# simple-differential-electrostatic-rev1.net
KiCad netlist of a schematic drawn in EAGLE
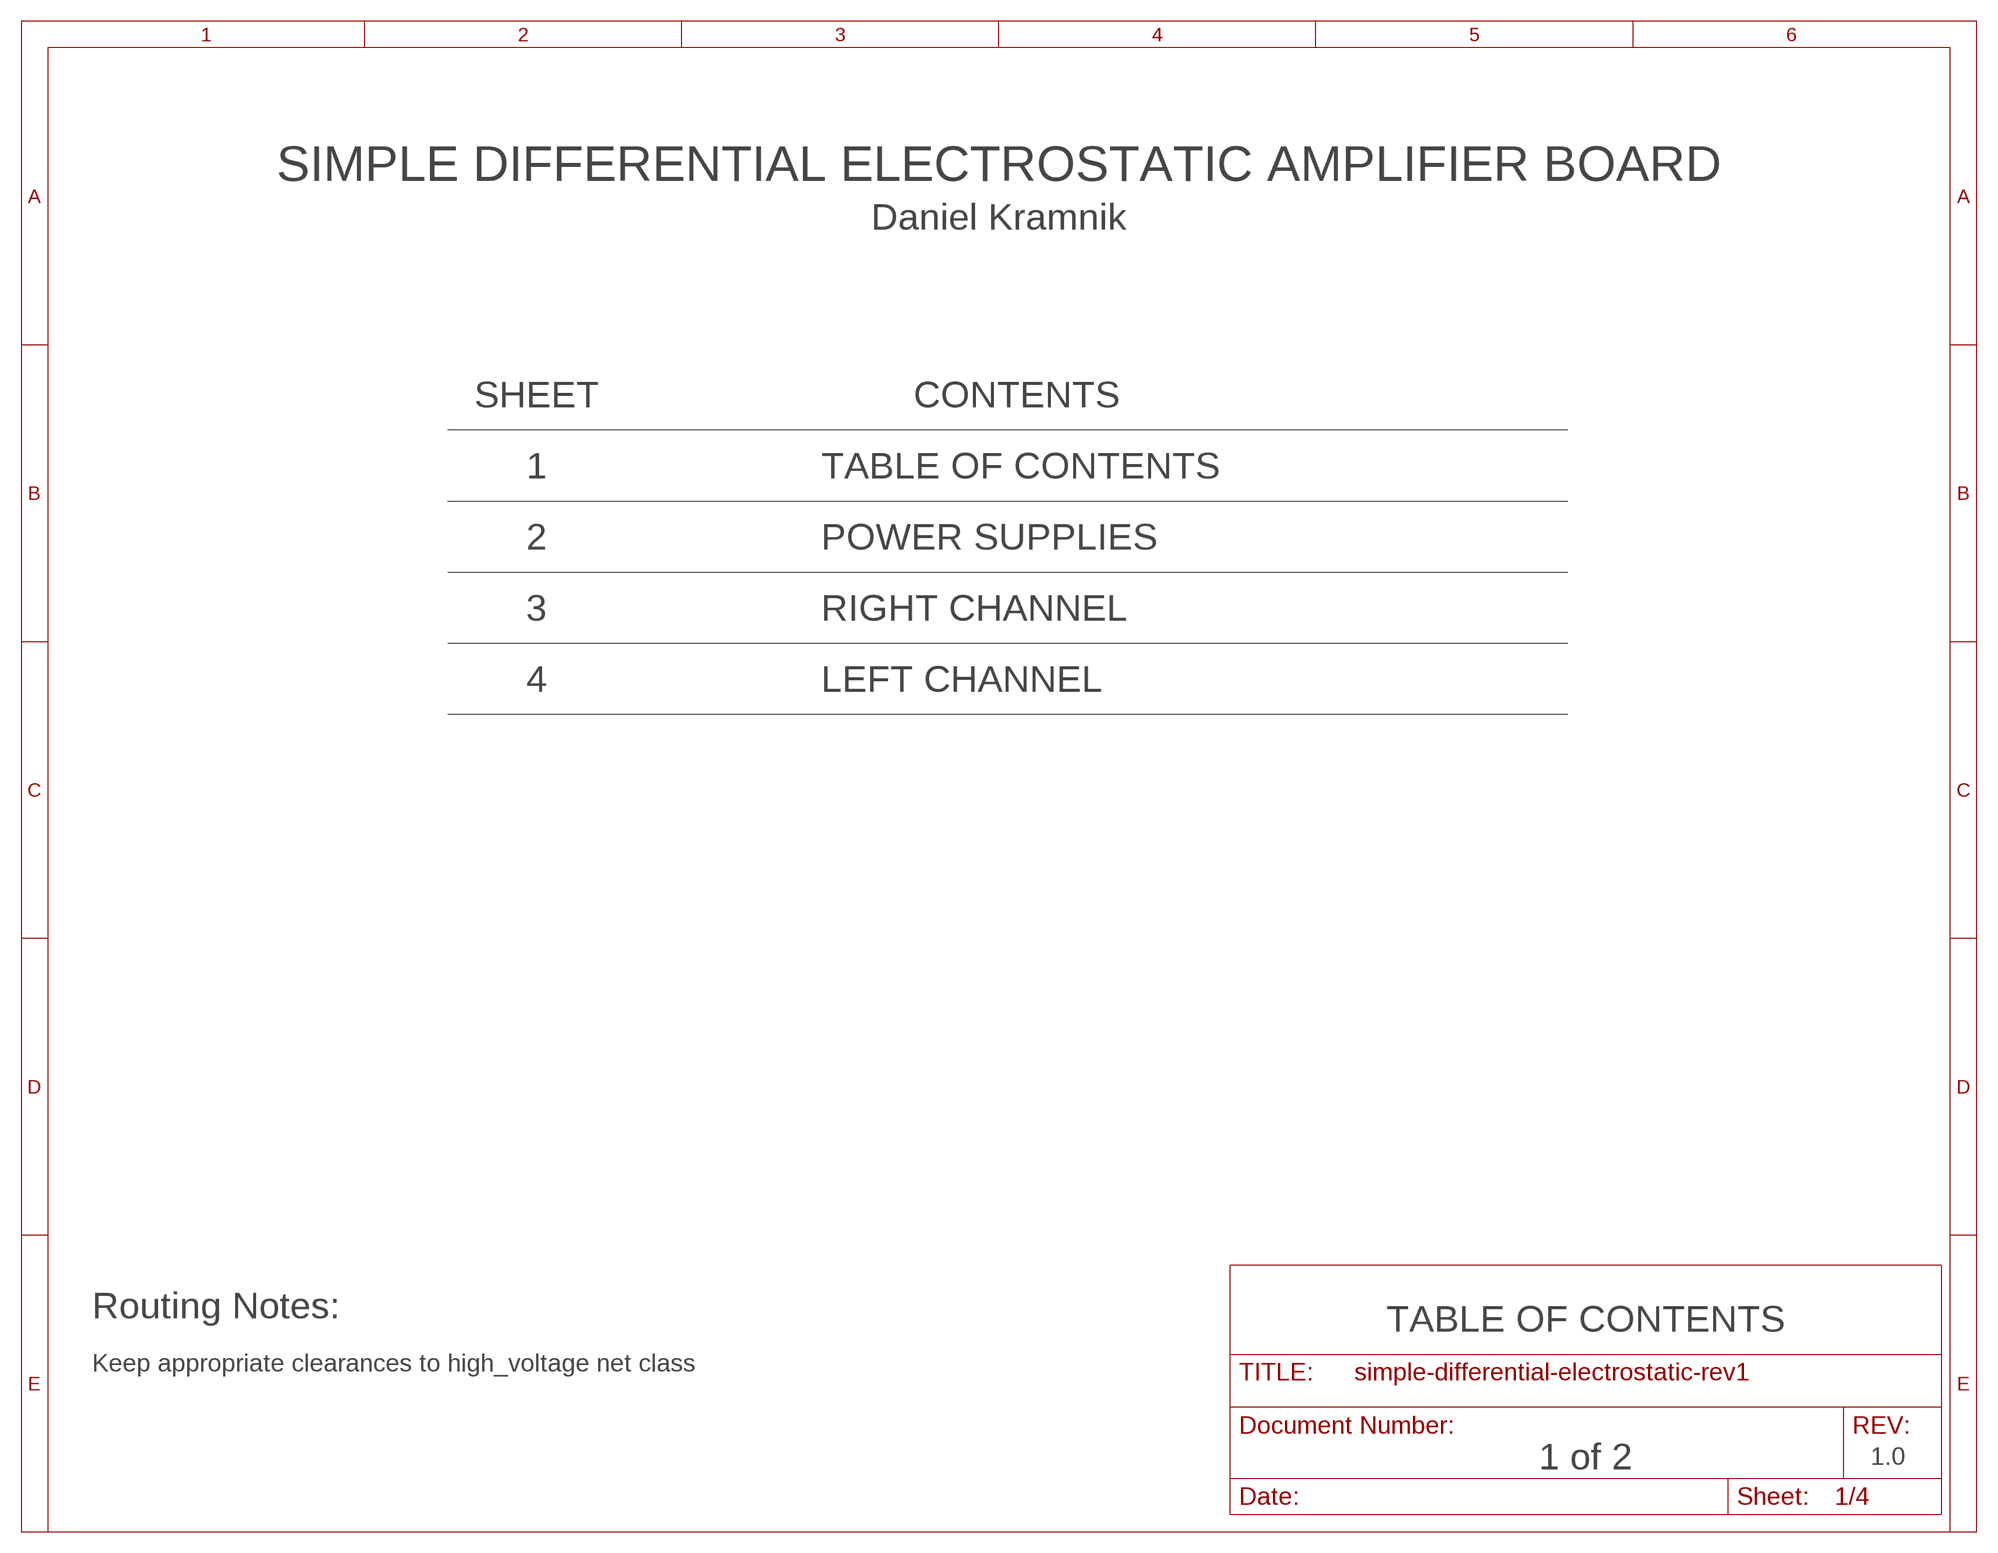
[diagram p0: schematic, sheet 1]
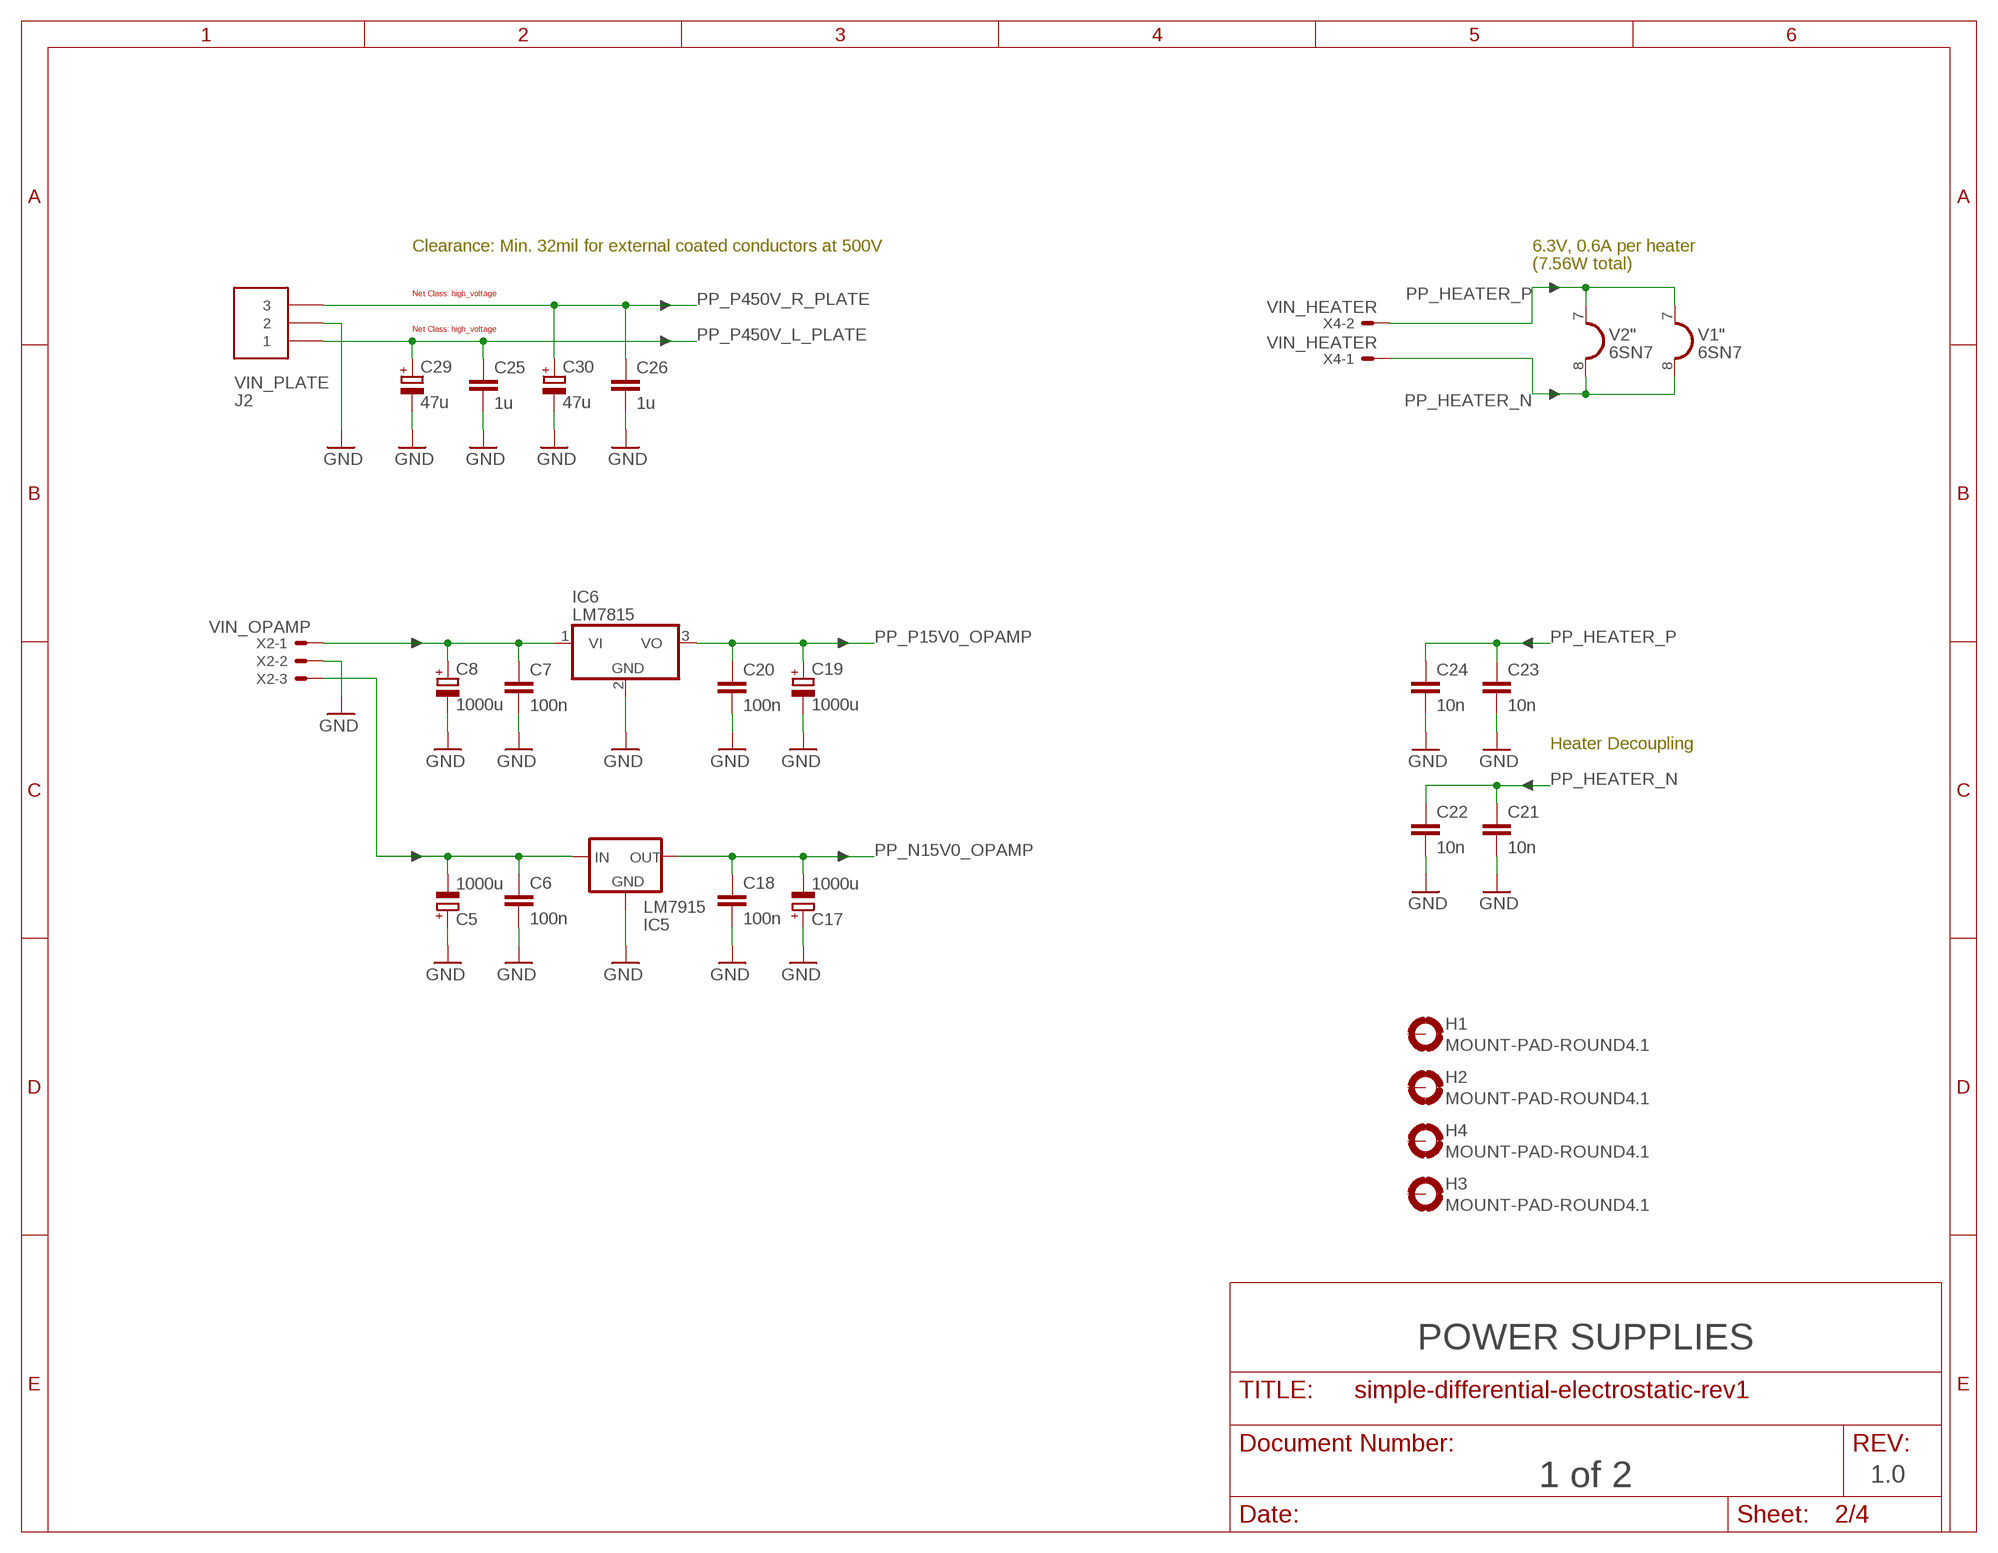
[diagram p1: schematic, sheet 2]
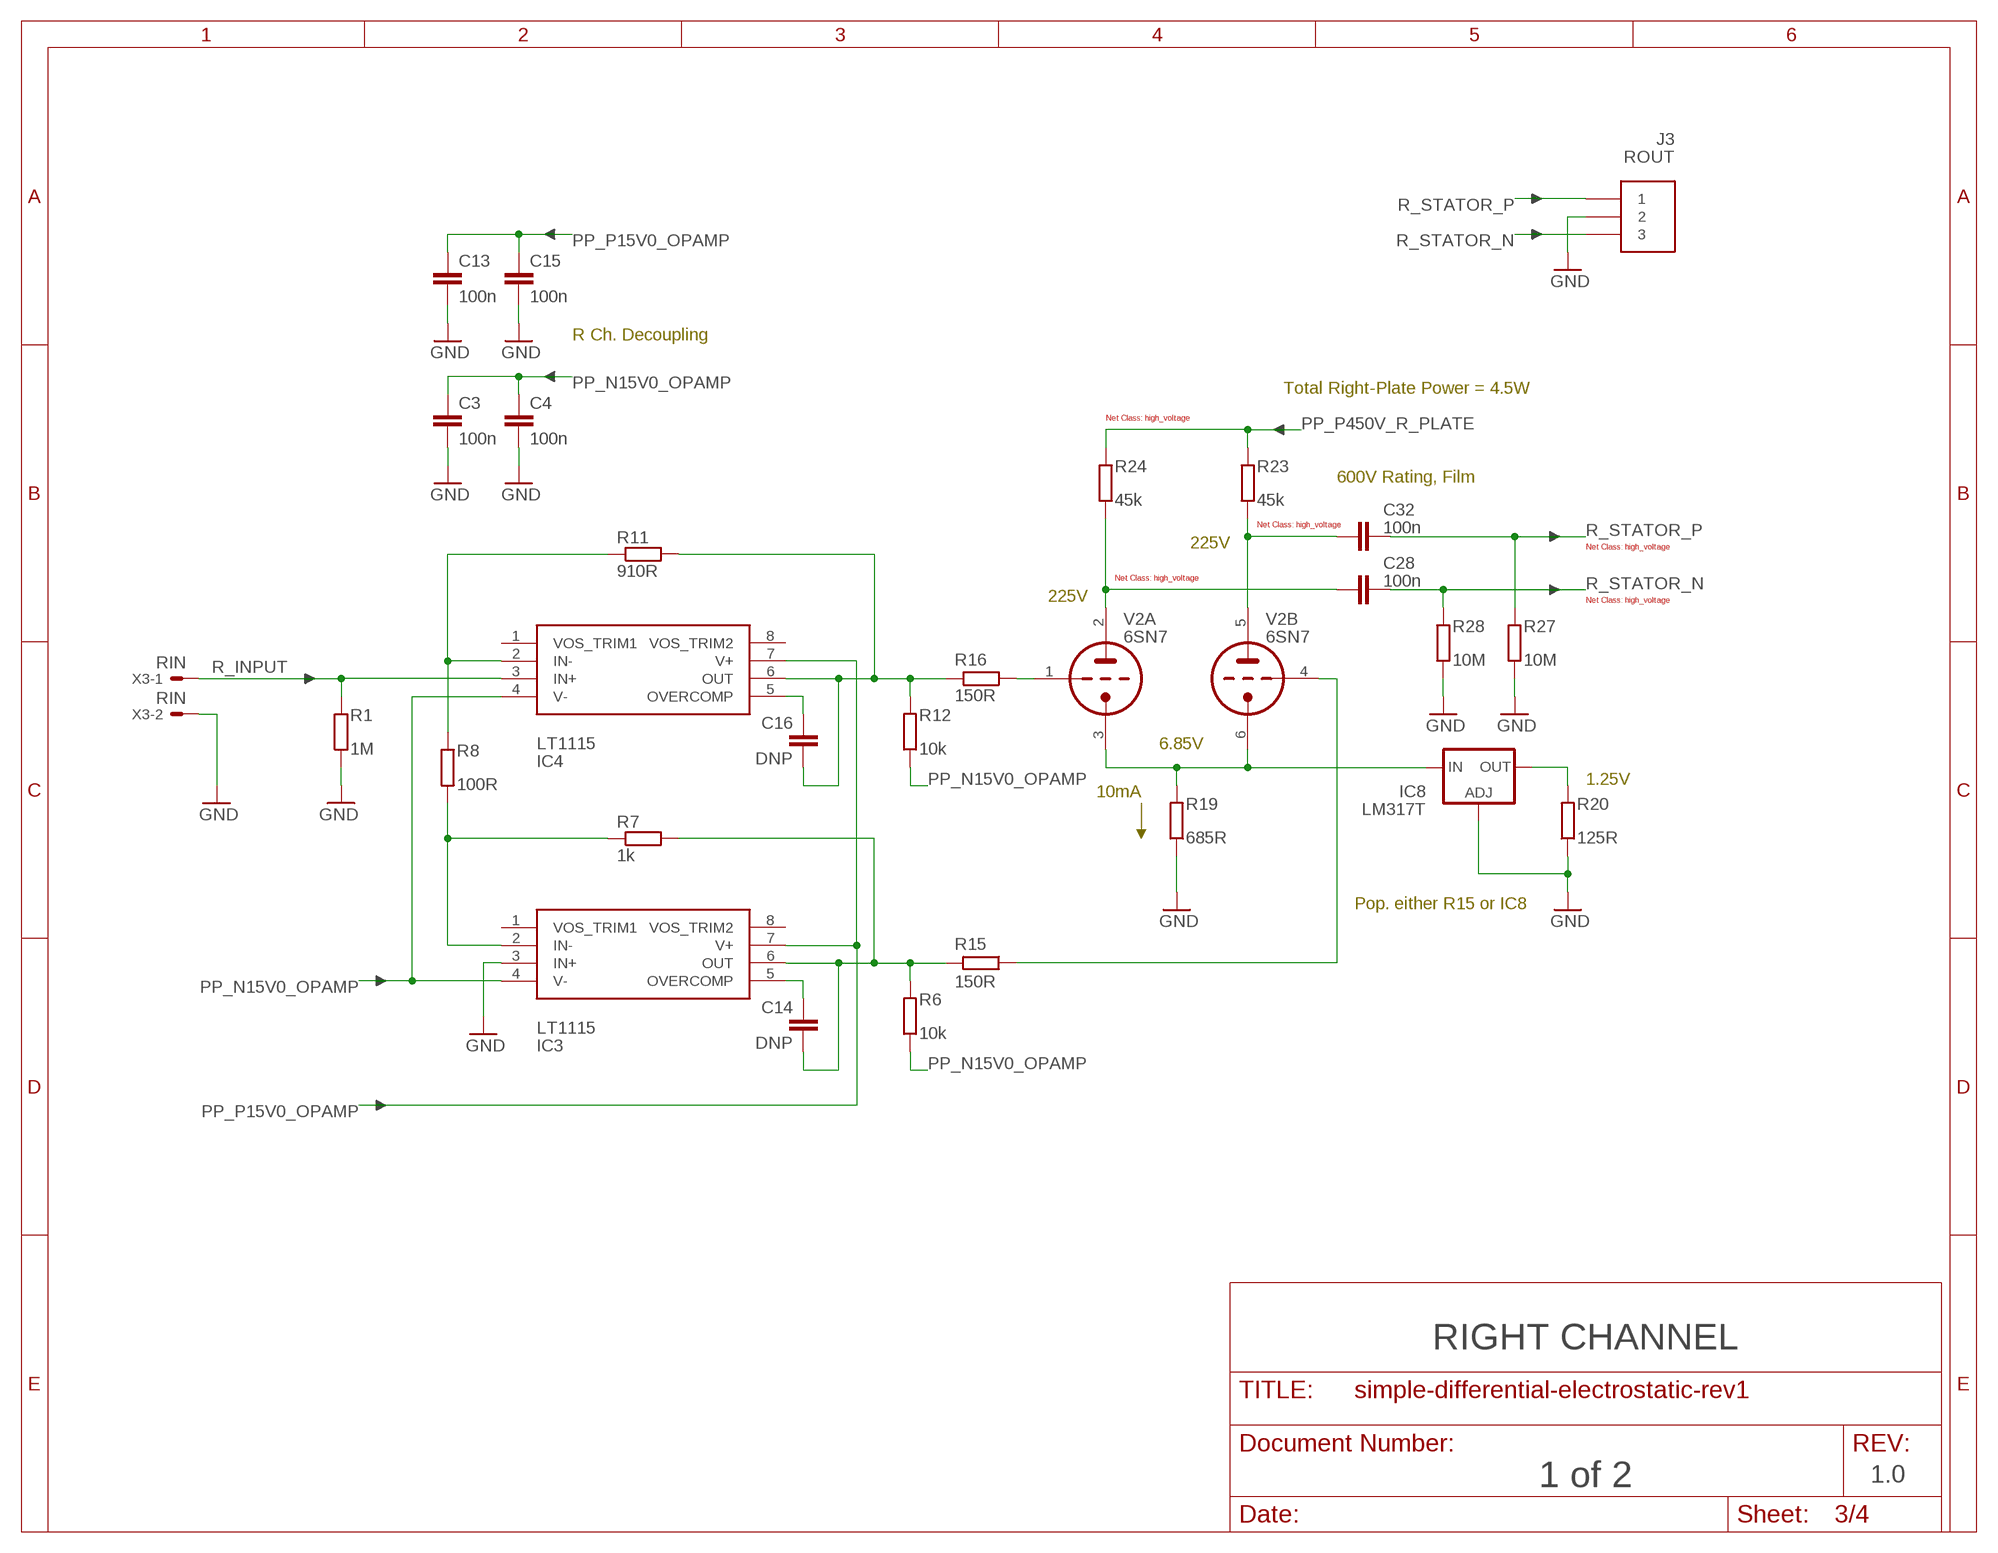
[diagram p2: schematic, sheet 3]
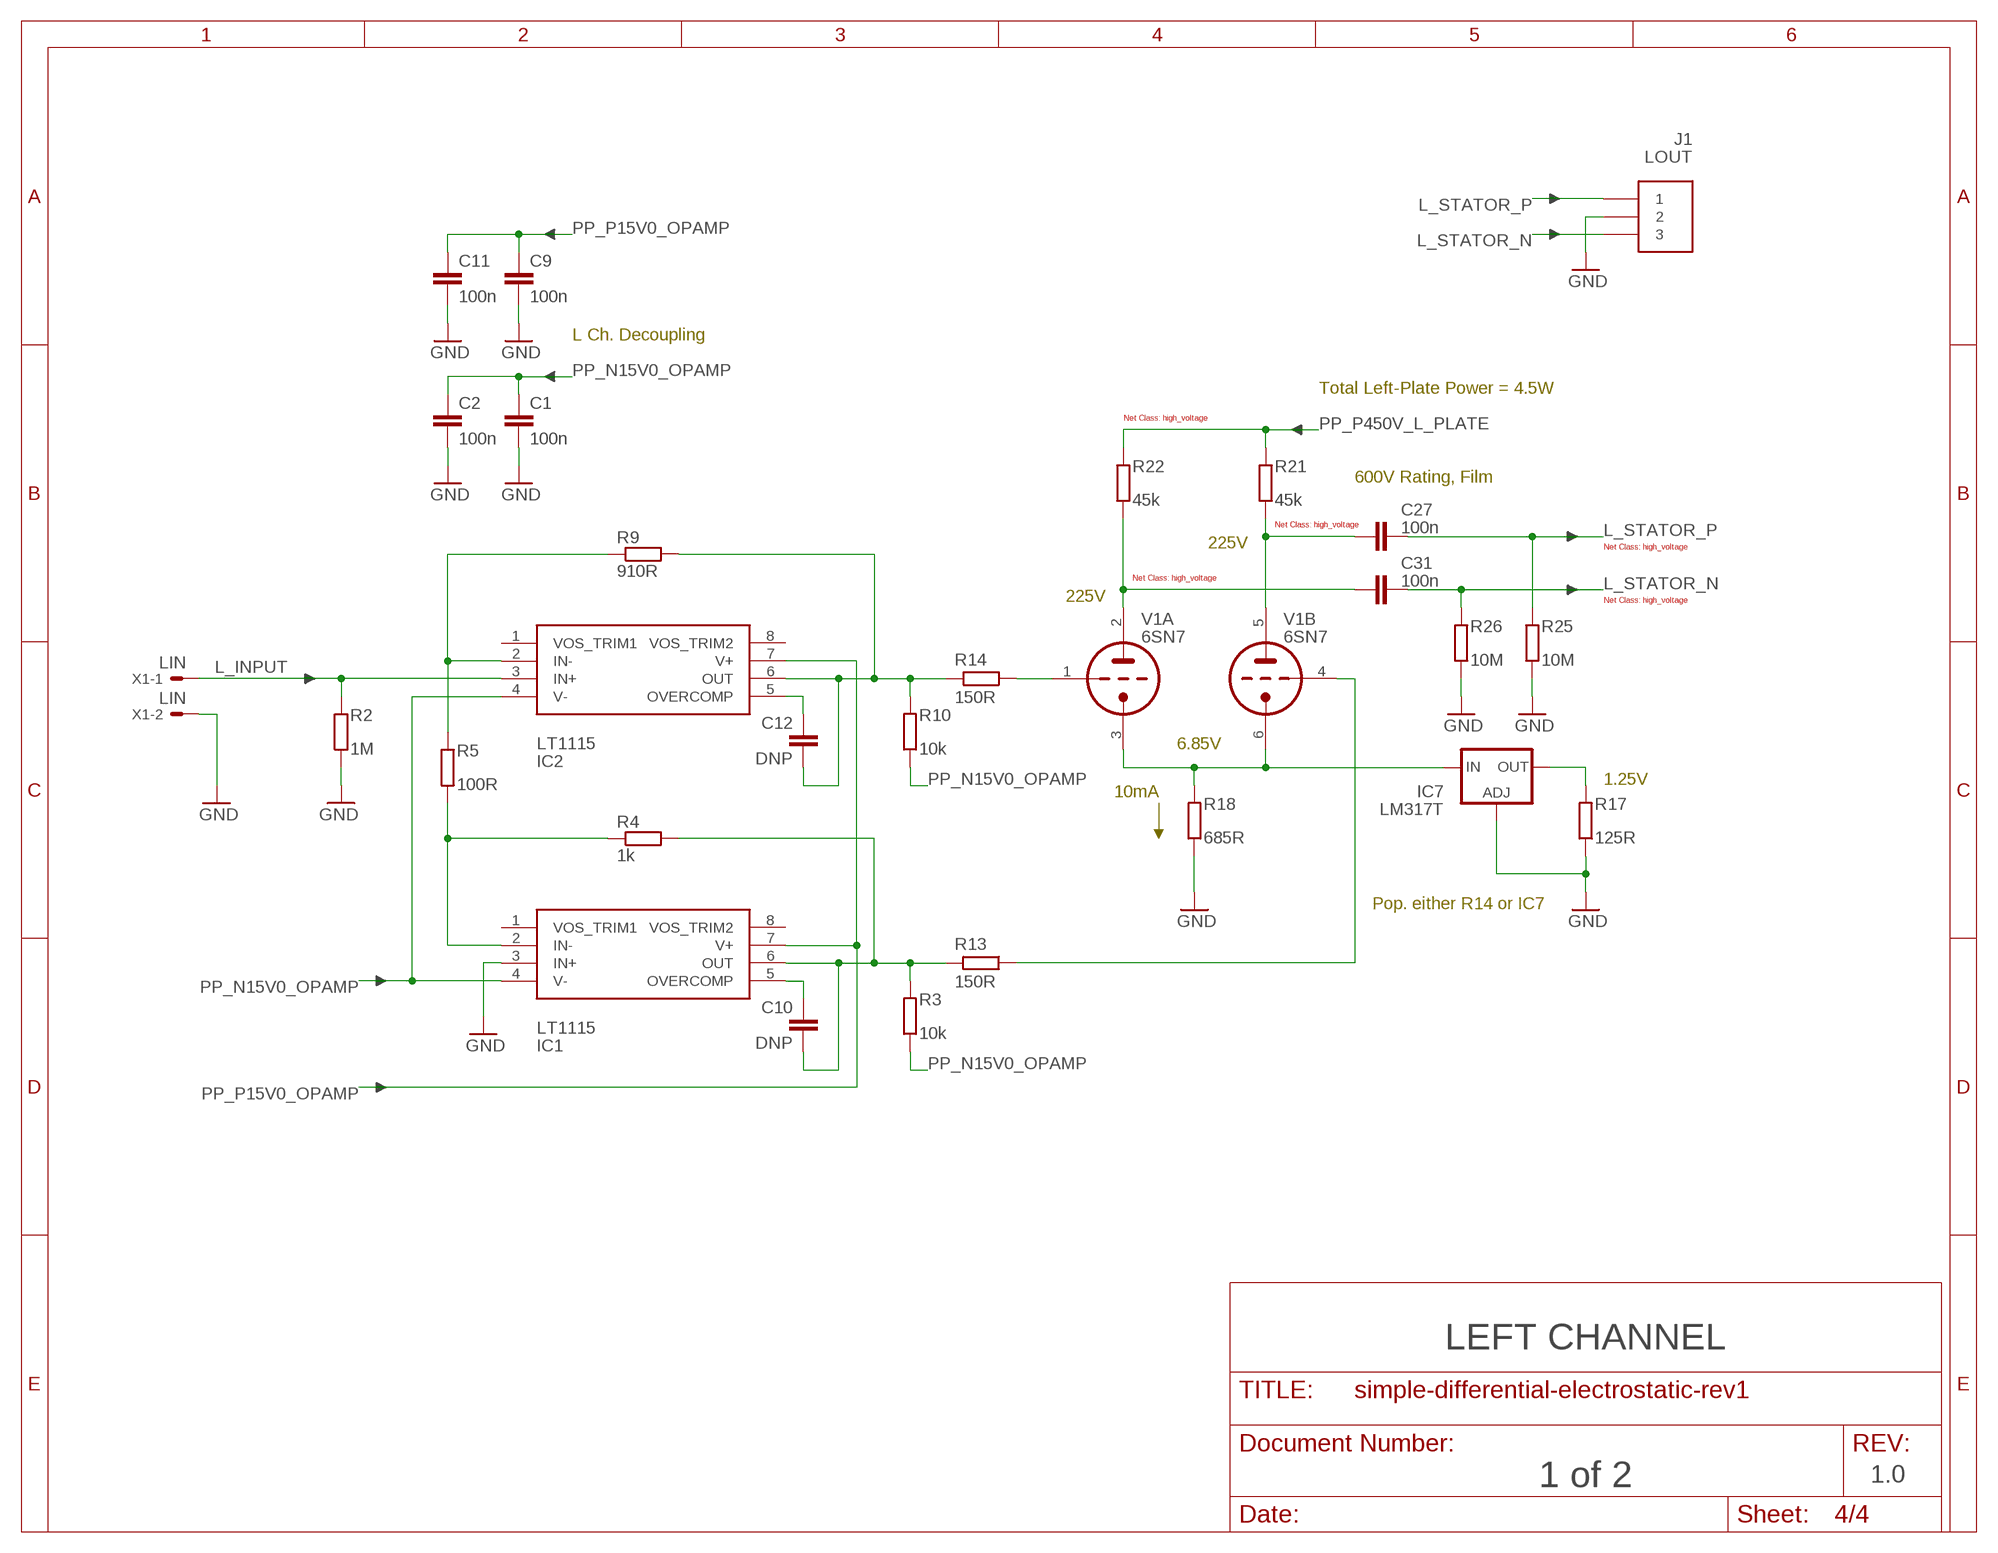
[diagram p3: schematic, sheet 4]

(export (version "E")
  (design (tool "Eeschema 10.0.6"))
  (components
    (comp (ref "C3")
      (value "100n")
      (footprint "eagle-import:C050-025X075")
      (libsource (lib "eagle-import") (part "C-EU050-025X075"))
    )
    (comp (ref "C4")
      (value "100n")
      (footprint "eagle-import:C050-025X075")
      (libsource (lib "eagle-import") (part "C-EU050-025X075"))
    )
    (comp (ref "C13")
      (value "100n")
      (footprint "eagle-import:C050-025X075")
      (libsource (lib "eagle-import") (part "C-EU050-025X075"))
    )
    (comp (ref "C14")
      (value "DNP")
      (footprint "eagle-import:C050-025X075")
      (libsource (lib "eagle-import") (part "C-EU050-025X075"))
    )
    (comp (ref "C15")
      (value "100n")
      (footprint "eagle-import:C050-025X075")
      (libsource (lib "eagle-import") (part "C-EU050-025X075"))
    )
    (comp (ref "C16")
      (value "DNP")
      (footprint "eagle-import:C050-025X075")
      (libsource (lib "eagle-import") (part "C-EU050-025X075"))
    )
    (comp (ref "C28")
      (value "100n")
      (footprint "eagle-import:C375-155X418")
      (libsource (lib "eagle-import") (part "C-EU375-155X418"))
    )
    (comp (ref "C32")
      (value "100n")
      (footprint "eagle-import:C375-155X418")
      (libsource (lib "eagle-import") (part "C-EU375-155X418"))
    )
    (comp (ref "IC3")
      (value "LT1115")
      (footprint "eagle-import:DIL08")
      (libsource (lib "eagle-import") (part "LT1115"))
    )
    (comp (ref "IC4")
      (value "LT1115")
      (footprint "eagle-import:DIL08")
      (libsource (lib "eagle-import") (part "LT1115"))
    )
    (comp (ref "IC8")
      (value "LM317T")
      (footprint "eagle-import:317TS")
      (libsource (lib "eagle-import") (part "LM317TS"))
    )
    (comp (ref "J3")
      (value "ROUT")
      (footprint "eagle-import:CONN_MOLEX_3PIN_MINI-FIT_JR")
      (libsource (lib "eagle-import") (part "CONN_MOLEX_3PIN_MINI-FIT_JR"))
    )
    (comp (ref "R1")
      (value "1M")
      (footprint "eagle-import:0309_10")
      (libsource (lib "eagle-import") (part "R-EU_0309/10"))
    )
    (comp (ref "R6")
      (value "10k")
      (footprint "eagle-import:0309_10")
      (libsource (lib "eagle-import") (part "R-EU_0309/10"))
    )
    (comp (ref "R7")
      (value "1k")
      (footprint "eagle-import:0309_10")
      (libsource (lib "eagle-import") (part "R-EU_0309/10"))
    )
    (comp (ref "R8")
      (value "100R")
      (footprint "eagle-import:0309_10")
      (libsource (lib "eagle-import") (part "R-EU_0309/10"))
    )
    (comp (ref "R11")
      (value "910R")
      (footprint "eagle-import:0309_10")
      (libsource (lib "eagle-import") (part "R-EU_0309/10"))
    )
    (comp (ref "R12")
      (value "10k")
      (footprint "eagle-import:0309_10")
      (libsource (lib "eagle-import") (part "R-EU_0309/10"))
    )
    (comp (ref "R15")
      (value "150R")
      (footprint "eagle-import:0309_10")
      (libsource (lib "eagle-import") (part "R-EU_0309/10"))
    )
    (comp (ref "R16")
      (value "150R")
      (footprint "eagle-import:0309_10")
      (libsource (lib "eagle-import") (part "R-EU_0309/10"))
    )
    (comp (ref "R19")
      (value "685R")
      (footprint "eagle-import:0309_10")
      (libsource (lib "eagle-import") (part "R-EU_0309/10"))
    )
    (comp (ref "R20")
      (value "125R")
      (footprint "eagle-import:0309_10")
      (libsource (lib "eagle-import") (part "R-EU_0309/10"))
    )
    (comp (ref "R23")
      (value "45k")
      (footprint "eagle-import:P0613_15")
      (libsource (lib "eagle-import") (part "R-EU_0613/15"))
    )
    (comp (ref "R24")
      (value "45k")
      (footprint "eagle-import:P0613_15")
      (libsource (lib "eagle-import") (part "R-EU_0613/15"))
    )
    (comp (ref "R27")
      (value "10M")
      (footprint "eagle-import:0309_10")
      (libsource (lib "eagle-import") (part "R-EU_0309/10"))
    )
    (comp (ref "R28")
      (value "10M")
      (footprint "eagle-import:0309_10")
      (libsource (lib "eagle-import") (part "R-EU_0309/10"))
    )
    (comp (ref "V2")
      (value "6SN7")
      (footprint "eagle-import:OKTAL")
      (libsource (lib "eagle-import") (part "6SN7GT-P"))
    )
    (comp (ref "X3")
      (value "RIN")
      (footprint "eagle-import:KK-156-2")
      (libsource (lib "eagle-import") (part "KK-156-2"))
    )
    (comp (ref "C5")
      (value "1000u")
      (footprint "eagle-import:E5-10,5")
      (libsource (lib "eagle-import") (part "CPOL-EUE5-10.5"))
    )
    (comp (ref "C6")
      (value "100n")
      (footprint "eagle-import:C050-025X075")
      (libsource (lib "eagle-import") (part "C-EU050-025X075"))
    )
    (comp (ref "C7")
      (value "100n")
      (footprint "eagle-import:C050-025X075")
      (libsource (lib "eagle-import") (part "C-EU050-025X075"))
    )
    (comp (ref "C8")
      (value "1000u")
      (footprint "eagle-import:E5-10,5")
      (libsource (lib "eagle-import") (part "CPOL-EUE5-10.5"))
    )
    (comp (ref "C17")
      (value "1000u")
      (footprint "eagle-import:E5-10,5")
      (libsource (lib "eagle-import") (part "CPOL-EUE5-10.5"))
    )
    (comp (ref "C18")
      (value "100n")
      (footprint "eagle-import:C050-025X075")
      (libsource (lib "eagle-import") (part "C-EU050-025X075"))
    )
    (comp (ref "C19")
      (value "1000u")
      (footprint "eagle-import:E5-10,5")
      (libsource (lib "eagle-import") (part "CPOL-EUE5-10.5"))
    )
    (comp (ref "C20")
      (value "100n")
      (footprint "eagle-import:C050-025X075")
      (libsource (lib "eagle-import") (part "C-EU050-025X075"))
    )
    (comp (ref "C21")
      (value "10n")
      (footprint "eagle-import:C050-025X075")
      (libsource (lib "eagle-import") (part "C-EU050-025X075"))
    )
    (comp (ref "C22")
      (value "10n")
      (footprint "eagle-import:C050-025X075")
      (libsource (lib "eagle-import") (part "C-EU050-025X075"))
    )
    (comp (ref "C23")
      (value "10n")
      (footprint "eagle-import:C050-025X075")
      (libsource (lib "eagle-import") (part "C-EU050-025X075"))
    )
    (comp (ref "C24")
      (value "10n")
      (footprint "eagle-import:C050-025X075")
      (libsource (lib "eagle-import") (part "C-EU050-025X075"))
    )
    (comp (ref "C25")
      (value "1u")
      (footprint "eagle-import:C325-137X374")
      (libsource (lib "eagle-import") (part "C-EU325-137X374"))
    )
    (comp (ref "C26")
      (value "1u")
      (footprint "eagle-import:C325-137X374")
      (libsource (lib "eagle-import") (part "C-EU325-137X374"))
    )
    (comp (ref "C29")
      (value "47u")
      (footprint "eagle-import:EB22,5D")
      (libsource (lib "eagle-import") (part "CPOL-EUE10-22.5"))
    )
    (comp (ref "C30")
      (value "47u")
      (footprint "eagle-import:EB22,5D")
      (libsource (lib "eagle-import") (part "CPOL-EUE10-22.5"))
    )
    (comp (ref "H1")
      (value "MOUNT-PAD-ROUND4.1")
      (footprint "eagle-import:4,1-PAD")
      (libsource (lib "eagle-import") (part "MOUNT-PAD-ROUND4.1"))
    )
    (comp (ref "H2")
      (value "MOUNT-PAD-ROUND4.1")
      (footprint "eagle-import:4,1-PAD")
      (libsource (lib "eagle-import") (part "MOUNT-PAD-ROUND4.1"))
    )
    (comp (ref "H3")
      (value "MOUNT-PAD-ROUND4.1")
      (footprint "eagle-import:4,1-PAD")
      (libsource (lib "eagle-import") (part "MOUNT-PAD-ROUND4.1"))
    )
    (comp (ref "H4")
      (value "MOUNT-PAD-ROUND4.1")
      (footprint "eagle-import:4,1-PAD")
      (libsource (lib "eagle-import") (part "MOUNT-PAD-ROUND4.1"))
    )
    (comp (ref "IC5")
      (value "LM7915")
      (footprint "eagle-import:79XXS")
      (libsource (lib "eagle-import") (part "79XXS"))
    )
    (comp (ref "IC6")
      (value "LM7815")
      (footprint "eagle-import:TO220V")
      (libsource (lib "eagle-import") (part "78TV15"))
    )
    (comp (ref "J2")
      (value "VIN_PLATE")
      (footprint "eagle-import:CONN_MOLEX_3PIN_MINI-FIT_JR")
      (libsource (lib "eagle-import") (part "CONN_MOLEX_3PIN_MINI-FIT_JR"))
    )
    (comp (ref "V1")
      (value "6SN7")
      (footprint "eagle-import:OKTAL")
      (libsource (lib "eagle-import") (part "6SN7GT-P"))
    )
    (comp (ref "X2")
      (value "VIN_OPAMP")
      (footprint "eagle-import:KK-156-3")
      (libsource (lib "eagle-import") (part "KK-156-3"))
    )
    (comp (ref "X4")
      (value "VIN_HEATER")
      (footprint "eagle-import:KK-156-2")
      (libsource (lib "eagle-import") (part "KK-156-2"))
    )
    (comp (ref "C1")
      (value "100n")
      (footprint "eagle-import:C050-025X075")
      (libsource (lib "eagle-import") (part "C-EU050-025X075"))
    )
    (comp (ref "C2")
      (value "100n")
      (footprint "eagle-import:C050-025X075")
      (libsource (lib "eagle-import") (part "C-EU050-025X075"))
    )
    (comp (ref "C9")
      (value "100n")
      (footprint "eagle-import:C050-025X075")
      (libsource (lib "eagle-import") (part "C-EU050-025X075"))
    )
    (comp (ref "C10")
      (value "DNP")
      (footprint "eagle-import:C050-025X075")
      (libsource (lib "eagle-import") (part "C-EU050-025X075"))
    )
    (comp (ref "C11")
      (value "100n")
      (footprint "eagle-import:C050-025X075")
      (libsource (lib "eagle-import") (part "C-EU050-025X075"))
    )
    (comp (ref "C12")
      (value "DNP")
      (footprint "eagle-import:C050-025X075")
      (libsource (lib "eagle-import") (part "C-EU050-025X075"))
    )
    (comp (ref "C27")
      (value "100n")
      (footprint "eagle-import:C375-155X418")
      (libsource (lib "eagle-import") (part "C-EU375-155X418"))
    )
    (comp (ref "C31")
      (value "100n")
      (footprint "eagle-import:C375-155X418")
      (libsource (lib "eagle-import") (part "C-EU375-155X418"))
    )
    (comp (ref "IC1")
      (value "LT1115")
      (footprint "eagle-import:DIL08")
      (libsource (lib "eagle-import") (part "LT1115"))
    )
    (comp (ref "IC2")
      (value "LT1115")
      (footprint "eagle-import:DIL08")
      (libsource (lib "eagle-import") (part "LT1115"))
    )
    (comp (ref "IC7")
      (value "LM317T")
      (footprint "eagle-import:317TS")
      (libsource (lib "eagle-import") (part "LM317TS"))
    )
    (comp (ref "J1")
      (value "LOUT")
      (footprint "eagle-import:CONN_MOLEX_3PIN_MINI-FIT_JR")
      (libsource (lib "eagle-import") (part "CONN_MOLEX_3PIN_MINI-FIT_JR"))
    )
    (comp (ref "R2")
      (value "1M")
      (footprint "eagle-import:0309_10")
      (libsource (lib "eagle-import") (part "R-EU_0309/10"))
    )
    (comp (ref "R3")
      (value "10k")
      (footprint "eagle-import:0309_10")
      (libsource (lib "eagle-import") (part "R-EU_0309/10"))
    )
    (comp (ref "R4")
      (value "1k")
      (footprint "eagle-import:0309_10")
      (libsource (lib "eagle-import") (part "R-EU_0309/10"))
    )
    (comp (ref "R5")
      (value "100R")
      (footprint "eagle-import:0309_10")
      (libsource (lib "eagle-import") (part "R-EU_0309/10"))
    )
    (comp (ref "R9")
      (value "910R")
      (footprint "eagle-import:0309_10")
      (libsource (lib "eagle-import") (part "R-EU_0309/10"))
    )
    (comp (ref "R10")
      (value "10k")
      (footprint "eagle-import:0309_10")
      (libsource (lib "eagle-import") (part "R-EU_0309/10"))
    )
    (comp (ref "R13")
      (value "150R")
      (footprint "eagle-import:0309_10")
      (libsource (lib "eagle-import") (part "R-EU_0309/10"))
    )
    (comp (ref "R14")
      (value "150R")
      (footprint "eagle-import:0309_10")
      (libsource (lib "eagle-import") (part "R-EU_0309/10"))
    )
    (comp (ref "R17")
      (value "125R")
      (footprint "eagle-import:0309_10")
      (libsource (lib "eagle-import") (part "R-EU_0309/10"))
    )
    (comp (ref "R18")
      (value "685R")
      (footprint "eagle-import:0309_10")
      (libsource (lib "eagle-import") (part "R-EU_0309/10"))
    )
    (comp (ref "R21")
      (value "45k")
      (footprint "eagle-import:P0613_15")
      (libsource (lib "eagle-import") (part "R-EU_0613/15"))
    )
    (comp (ref "R22")
      (value "45k")
      (footprint "eagle-import:P0613_15")
      (libsource (lib "eagle-import") (part "R-EU_0613/15"))
    )
    (comp (ref "R25")
      (value "10M")
      (footprint "eagle-import:0309_10")
      (libsource (lib "eagle-import") (part "R-EU_0309/10"))
    )
    (comp (ref "R26")
      (value "10M")
      (footprint "eagle-import:0309_10")
      (libsource (lib "eagle-import") (part "R-EU_0309/10"))
    )
    (comp (ref "X1")
      (value "LIN")
      (footprint "eagle-import:KK-156-2")
      (libsource (lib "eagle-import") (part "KK-156-2"))
    )
  )
  (nets
    (net (code "1") (name "GND") (class "Default")
      (node (ref "C1") (pin "2") (pinfunction "2_2") (pintype "passive"))
      (node (ref "C11") (pin "2") (pinfunction "2_2") (pintype "passive"))
      (node (ref "C13") (pin "2") (pinfunction "2_2") (pintype "passive"))
      (node (ref "C15") (pin "2") (pinfunction "2_2") (pintype "passive"))
      (node (ref "C17") (pin "+") (pinfunction "+_+") (pintype "passive"))
      (node (ref "C18") (pin "2") (pinfunction "2_2") (pintype "passive"))
      (node (ref "C19") (pin "-") (pinfunction "-_-") (pintype "passive"))
      (node (ref "C2") (pin "2") (pinfunction "2_2") (pintype "passive"))
      (node (ref "C20") (pin "2") (pinfunction "2_2") (pintype "passive"))
      (node (ref "C21") (pin "2") (pinfunction "2_2") (pintype "passive"))
      (node (ref "C22") (pin "2") (pinfunction "2_2") (pintype "passive"))
      (node (ref "C23") (pin "2") (pinfunction "2_2") (pintype "passive"))
      (node (ref "C24") (pin "2") (pinfunction "2_2") (pintype "passive"))
      (node (ref "C25") (pin "2") (pinfunction "2_2") (pintype "passive"))
      (node (ref "C26") (pin "2") (pinfunction "2_2") (pintype "passive"))
      (node (ref "C29") (pin "-") (pinfunction "-_-") (pintype "passive"))
      (node (ref "C3") (pin "2") (pinfunction "2_2") (pintype "passive"))
      (node (ref "C30") (pin "-") (pinfunction "-_-") (pintype "passive"))
      (node (ref "C4") (pin "2") (pinfunction "2_2") (pintype "passive"))
      (node (ref "C5") (pin "+") (pinfunction "+_+") (pintype "passive"))
      (node (ref "C6") (pin "2") (pinfunction "2_2") (pintype "passive"))
      (node (ref "C7") (pin "2") (pinfunction "2_2") (pintype "passive"))
      (node (ref "C8") (pin "-") (pinfunction "-_-") (pintype "passive"))
      (node (ref "C9") (pin "2") (pinfunction "2_2") (pintype "passive"))
      (node (ref "IC1") (pin "3") (pinfunction "IN+_3") (pintype "bidirectional"))
      (node (ref "IC3") (pin "3") (pinfunction "IN+_3") (pintype "bidirectional"))
      (node (ref "IC5") (pin "GND") (pinfunction "GND_GND") (pintype "input"))
      (node (ref "IC6") (pin "2") (pinfunction "GND_2") (pintype "passive"))
      (node (ref "IC7") (pin "1") (pinfunction "ADJ_1") (pintype "input"))
      (node (ref "IC8") (pin "1") (pinfunction "ADJ_1") (pintype "input"))
      (node (ref "J1") (pin "2") (pinfunction "2_2") (pintype "bidirectional"))
      (node (ref "J2") (pin "2") (pinfunction "2_2") (pintype "bidirectional"))
      (node (ref "J3") (pin "2") (pinfunction "2_2") (pintype "bidirectional"))
      (node (ref "R1") (pin "1") (pinfunction "1_1") (pintype "passive"))
      (node (ref "R17") (pin "1") (pinfunction "1_1") (pintype "passive"))
      (node (ref "R18") (pin "1") (pinfunction "1_1") (pintype "passive"))
      (node (ref "R19") (pin "1") (pinfunction "1_1") (pintype "passive"))
      (node (ref "R2") (pin "1") (pinfunction "1_1") (pintype "passive"))
      (node (ref "R20") (pin "1") (pinfunction "1_1") (pintype "passive"))
      (node (ref "R25") (pin "1") (pinfunction "1_1") (pintype "passive"))
      (node (ref "R26") (pin "1") (pinfunction "1_1") (pintype "passive"))
      (node (ref "R27") (pin "1") (pinfunction "1_1") (pintype "passive"))
      (node (ref "R28") (pin "1") (pinfunction "1_1") (pintype "passive"))
      (node (ref "X1") (pin "2") (pinfunction "S_2") (pintype "passive"))
      (node (ref "X2") (pin "2") (pinfunction "S_2") (pintype "passive"))
      (node (ref "X3") (pin "2") (pinfunction "S_2") (pintype "passive"))
    )
    (net (code "2") (name "L_INPUT") (class "Default")
      (node (ref "IC2") (pin "3") (pinfunction "IN+_3") (pintype "bidirectional"))
      (node (ref "R2") (pin "2") (pinfunction "2_2") (pintype "passive"))
      (node (ref "X1") (pin "1") (pinfunction "S_1") (pintype "passive"))
    )
    (net (code "3") (name "L_STATOR_N") (class "Default")
      (node (ref "C31") (pin "2") (pinfunction "2_2") (pintype "passive"))
      (node (ref "J1") (pin "3") (pinfunction "3_3") (pintype "bidirectional"))
      (node (ref "R26") (pin "2") (pinfunction "2_2") (pintype "passive"))
    )
    (net (code "4") (name "L_STATOR_P") (class "Default")
      (node (ref "C27") (pin "2") (pinfunction "2_2") (pintype "passive"))
      (node (ref "J1") (pin "1") (pinfunction "1_1") (pintype "bidirectional"))
      (node (ref "R25") (pin "2") (pinfunction "2_2") (pintype "passive"))
    )
    (net (code "5") (name "Net-(IC1-IN-)") (class "Default")
      (node (ref "IC1") (pin "2") (pinfunction "IN-_2") (pintype "bidirectional"))
      (node (ref "R4") (pin "1") (pinfunction "1_1") (pintype "passive"))
      (node (ref "R5") (pin "2") (pinfunction "2_2") (pintype "passive"))
    )
    (net (code "6") (name "Net-(IC1-OUT)") (class "Default")
      (node (ref "C10") (pin "2") (pinfunction "2_2") (pintype "passive"))
      (node (ref "IC1") (pin "6") (pinfunction "OUT_6") (pintype "bidirectional"))
      (node (ref "R13") (pin "2") (pinfunction "2_2") (pintype "passive"))
      (node (ref "R3") (pin "2") (pinfunction "2_2") (pintype "passive"))
      (node (ref "R4") (pin "2") (pinfunction "2_2") (pintype "passive"))
    )
    (net (code "7") (name "Net-(IC1-OVERCOMP)") (class "Default")
      (node (ref "C10") (pin "1") (pinfunction "1_1") (pintype "passive"))
      (node (ref "IC1") (pin "5") (pinfunction "OVERCOMP_5") (pintype "bidirectional"))
    )
    (net (code "8") (name "Net-(IC2-IN-)") (class "Default")
      (node (ref "IC2") (pin "2") (pinfunction "IN-_2") (pintype "bidirectional"))
      (node (ref "R5") (pin "1") (pinfunction "1_1") (pintype "passive"))
      (node (ref "R9") (pin "1") (pinfunction "1_1") (pintype "passive"))
    )
    (net (code "9") (name "Net-(IC2-OUT)") (class "Default")
      (node (ref "C12") (pin "2") (pinfunction "2_2") (pintype "passive"))
      (node (ref "IC2") (pin "6") (pinfunction "OUT_6") (pintype "bidirectional"))
      (node (ref "R10") (pin "2") (pinfunction "2_2") (pintype "passive"))
      (node (ref "R14") (pin "2") (pinfunction "2_2") (pintype "passive"))
      (node (ref "R9") (pin "2") (pinfunction "2_2") (pintype "passive"))
    )
    (net (code "10") (name "Net-(IC2-OVERCOMP)") (class "Default")
      (node (ref "C12") (pin "1") (pinfunction "1_1") (pintype "passive"))
      (node (ref "IC2") (pin "5") (pinfunction "OVERCOMP_5") (pintype "bidirectional"))
    )
    (net (code "11") (name "Net-(IC3-IN-)") (class "Default")
      (node (ref "IC3") (pin "2") (pinfunction "IN-_2") (pintype "bidirectional"))
      (node (ref "R7") (pin "1") (pinfunction "1_1") (pintype "passive"))
      (node (ref "R8") (pin "2") (pinfunction "2_2") (pintype "passive"))
    )
    (net (code "12") (name "Net-(IC3-OUT)") (class "Default")
      (node (ref "C14") (pin "2") (pinfunction "2_2") (pintype "passive"))
      (node (ref "IC3") (pin "6") (pinfunction "OUT_6") (pintype "bidirectional"))
      (node (ref "R15") (pin "2") (pinfunction "2_2") (pintype "passive"))
      (node (ref "R6") (pin "2") (pinfunction "2_2") (pintype "passive"))
      (node (ref "R7") (pin "2") (pinfunction "2_2") (pintype "passive"))
    )
    (net (code "13") (name "Net-(IC3-OVERCOMP)") (class "Default")
      (node (ref "C14") (pin "1") (pinfunction "1_1") (pintype "passive"))
      (node (ref "IC3") (pin "5") (pinfunction "OVERCOMP_5") (pintype "bidirectional"))
    )
    (net (code "14") (name "Net-(IC4-IN-)") (class "Default")
      (node (ref "IC4") (pin "2") (pinfunction "IN-_2") (pintype "bidirectional"))
      (node (ref "R11") (pin "1") (pinfunction "1_1") (pintype "passive"))
      (node (ref "R8") (pin "1") (pinfunction "1_1") (pintype "passive"))
    )
    (net (code "15") (name "Net-(IC4-OUT)") (class "Default")
      (node (ref "C16") (pin "2") (pinfunction "2_2") (pintype "passive"))
      (node (ref "IC4") (pin "6") (pinfunction "OUT_6") (pintype "bidirectional"))
      (node (ref "R11") (pin "2") (pinfunction "2_2") (pintype "passive"))
      (node (ref "R12") (pin "2") (pinfunction "2_2") (pintype "passive"))
      (node (ref "R16") (pin "2") (pinfunction "2_2") (pintype "passive"))
    )
    (net (code "16") (name "Net-(IC4-OVERCOMP)") (class "Default")
      (node (ref "C16") (pin "1") (pinfunction "1_1") (pintype "passive"))
      (node (ref "IC4") (pin "5") (pinfunction "OVERCOMP_5") (pintype "bidirectional"))
    )
    (net (code "17") (name "Net-(IC6-VI)") (class "Default")
      (node (ref "C7") (pin "1") (pinfunction "1_1") (pintype "passive"))
      (node (ref "C8") (pin "+") (pinfunction "+_+") (pintype "passive"))
      (node (ref "IC6") (pin "1") (pinfunction "VI_1") (pintype "input"))
      (node (ref "X2") (pin "1") (pinfunction "S_1") (pintype "passive"))
    )
    (net (code "18") (name "Net-(IC7-IN)") (class "Default")
      (node (ref "IC7") (pin "3") (pinfunction "IN_3") (pintype "input"))
      (node (ref "R18") (pin "2") (pinfunction "2_2") (pintype "passive"))
      (node (ref "V1") (pin "3") (pinfunction "TK_3") (pintype "passive"))
      (node (ref "V1") (pin "6") (pinfunction "TK_6") (pintype "passive"))
    )
    (net (code "19") (name "Net-(IC7-OUT)") (class "Default")
      (node (ref "IC7") (pin "2") (pinfunction "OUT_2") (pintype "passive"))
      (node (ref "R17") (pin "2") (pinfunction "2_2") (pintype "passive"))
    )
    (net (code "20") (name "Net-(IC8-IN)") (class "Default")
      (node (ref "IC8") (pin "3") (pinfunction "IN_3") (pintype "input"))
      (node (ref "R19") (pin "2") (pinfunction "2_2") (pintype "passive"))
      (node (ref "V2") (pin "3") (pinfunction "TK_3") (pintype "passive"))
      (node (ref "V2") (pin "6") (pinfunction "TK_6") (pintype "passive"))
    )
    (net (code "21") (name "Net-(IC8-OUT)") (class "Default")
      (node (ref "IC8") (pin "2") (pinfunction "OUT_2") (pintype "passive"))
      (node (ref "R20") (pin "2") (pinfunction "2_2") (pintype "passive"))
    )
    (net (code "22") (name "Net-(V1B-TA)") (class "Default")
      (node (ref "C31") (pin "1") (pinfunction "1_1") (pintype "passive"))
      (node (ref "R22") (pin "1") (pinfunction "1_1") (pintype "passive"))
      (node (ref "V1") (pin "2") (pinfunction "TA_2") (pintype "passive"))
    )
    (net (code "23") (name "Net-(V1B-TG)") (class "Default")
      (node (ref "R14") (pin "1") (pinfunction "1_1") (pintype "passive"))
      (node (ref "V1") (pin "1") (pinfunction "TG_1") (pintype "passive"))
    )
    (net (code "24") (name "Net-(V1C-TA)") (class "Default")
      (node (ref "C27") (pin "1") (pinfunction "1_1") (pintype "passive"))
      (node (ref "R21") (pin "1") (pinfunction "1_1") (pintype "passive"))
      (node (ref "V1") (pin "5") (pinfunction "TA_5") (pintype "passive"))
    )
    (net (code "25") (name "Net-(V1C-TG)") (class "Default")
      (node (ref "R13") (pin "1") (pinfunction "1_1") (pintype "passive"))
      (node (ref "V1") (pin "4") (pinfunction "TG_4") (pintype "passive"))
    )
    (net (code "26") (name "Net-(V2B-TA)") (class "Default")
      (node (ref "C28") (pin "1") (pinfunction "1_1") (pintype "passive"))
      (node (ref "R24") (pin "1") (pinfunction "1_1") (pintype "passive"))
      (node (ref "V2") (pin "2") (pinfunction "TA_2") (pintype "passive"))
    )
    (net (code "27") (name "Net-(V2B-TG)") (class "Default")
      (node (ref "R16") (pin "1") (pinfunction "1_1") (pintype "passive"))
      (node (ref "V2") (pin "1") (pinfunction "TG_1") (pintype "passive"))
    )
    (net (code "28") (name "Net-(V2C-TA)") (class "Default")
      (node (ref "C32") (pin "1") (pinfunction "1_1") (pintype "passive"))
      (node (ref "R23") (pin "1") (pinfunction "1_1") (pintype "passive"))
      (node (ref "V2") (pin "5") (pinfunction "TA_5") (pintype "passive"))
    )
    (net (code "29") (name "Net-(V2C-TG)") (class "Default")
      (node (ref "R15") (pin "1") (pinfunction "1_1") (pintype "passive"))
      (node (ref "V2") (pin "4") (pinfunction "TG_4") (pintype "passive"))
    )
    (net (code "30") (name "Net-(X2C-S)") (class "Default")
      (node (ref "C5") (pin "-") (pinfunction "-_-") (pintype "passive"))
      (node (ref "C6") (pin "1") (pinfunction "1_1") (pintype "passive"))
      (node (ref "IC5") (pin "IN") (pinfunction "IN_IN") (pintype "input"))
      (node (ref "X2") (pin "3") (pinfunction "S_3") (pintype "passive"))
    )
    (net (code "31") (name "PP_HEATER_N") (class "Default")
      (node (ref "C21") (pin "1") (pinfunction "1_1") (pintype "passive"))
      (node (ref "C22") (pin "1") (pinfunction "1_1") (pintype "passive"))
      (node (ref "V1") (pin "8") (pinfunction "H2_8") (pintype "passive"))
      (node (ref "V2") (pin "8") (pinfunction "H2_8") (pintype "passive"))
      (node (ref "X4") (pin "1") (pinfunction "S_1") (pintype "passive"))
    )
    (net (code "32") (name "PP_HEATER_P") (class "Default")
      (node (ref "C23") (pin "1") (pinfunction "1_1") (pintype "passive"))
      (node (ref "C24") (pin "1") (pinfunction "1_1") (pintype "passive"))
      (node (ref "V1") (pin "7") (pinfunction "H1_7") (pintype "passive"))
      (node (ref "V2") (pin "7") (pinfunction "H1_7") (pintype "passive"))
      (node (ref "X4") (pin "2") (pinfunction "S_2") (pintype "passive"))
    )
    (net (code "33") (name "PP_N15V0_OPAMP") (class "Default")
      (node (ref "C1") (pin "1") (pinfunction "1_1") (pintype "passive"))
      (node (ref "C17") (pin "-") (pinfunction "-_-") (pintype "passive"))
      (node (ref "C18") (pin "1") (pinfunction "1_1") (pintype "passive"))
      (node (ref "C2") (pin "1") (pinfunction "1_1") (pintype "passive"))
      (node (ref "C3") (pin "1") (pinfunction "1_1") (pintype "passive"))
      (node (ref "C4") (pin "1") (pinfunction "1_1") (pintype "passive"))
      (node (ref "IC1") (pin "4") (pinfunction "V-_4") (pintype "bidirectional"))
      (node (ref "IC2") (pin "4") (pinfunction "V-_4") (pintype "bidirectional"))
      (node (ref "IC3") (pin "4") (pinfunction "V-_4") (pintype "bidirectional"))
      (node (ref "IC4") (pin "4") (pinfunction "V-_4") (pintype "bidirectional"))
      (node (ref "IC5") (pin "OUT") (pinfunction "OUT_OUT") (pintype "passive"))
      (node (ref "R10") (pin "1") (pinfunction "1_1") (pintype "passive"))
      (node (ref "R12") (pin "1") (pinfunction "1_1") (pintype "passive"))
      (node (ref "R3") (pin "1") (pinfunction "1_1") (pintype "passive"))
      (node (ref "R6") (pin "1") (pinfunction "1_1") (pintype "passive"))
    )
    (net (code "34") (name "PP_P15V0_OPAMP") (class "Default")
      (node (ref "C11") (pin "1") (pinfunction "1_1") (pintype "passive"))
      (node (ref "C13") (pin "1") (pinfunction "1_1") (pintype "passive"))
      (node (ref "C15") (pin "1") (pinfunction "1_1") (pintype "passive"))
      (node (ref "C19") (pin "+") (pinfunction "+_+") (pintype "passive"))
      (node (ref "C20") (pin "1") (pinfunction "1_1") (pintype "passive"))
      (node (ref "C9") (pin "1") (pinfunction "1_1") (pintype "passive"))
      (node (ref "IC1") (pin "7") (pinfunction "V+_7") (pintype "bidirectional"))
      (node (ref "IC2") (pin "7") (pinfunction "V+_7") (pintype "bidirectional"))
      (node (ref "IC3") (pin "7") (pinfunction "V+_7") (pintype "bidirectional"))
      (node (ref "IC4") (pin "7") (pinfunction "V+_7") (pintype "bidirectional"))
      (node (ref "IC6") (pin "3") (pinfunction "VO_3") (pintype "passive"))
    )
    (net (code "35") (name "PP_P450V_L_PLATE") (class "Default")
      (node (ref "C25") (pin "1") (pinfunction "1_1") (pintype "passive"))
      (node (ref "C29") (pin "+") (pinfunction "+_+") (pintype "passive"))
      (node (ref "J2") (pin "1") (pinfunction "1_1") (pintype "bidirectional"))
      (node (ref "R21") (pin "2") (pinfunction "2_2") (pintype "passive"))
      (node (ref "R22") (pin "2") (pinfunction "2_2") (pintype "passive"))
    )
    (net (code "36") (name "PP_P450V_R_PLATE") (class "Default")
      (node (ref "C26") (pin "1") (pinfunction "1_1") (pintype "passive"))
      (node (ref "C30") (pin "+") (pinfunction "+_+") (pintype "passive"))
      (node (ref "J2") (pin "3") (pinfunction "3_3") (pintype "bidirectional"))
      (node (ref "R23") (pin "2") (pinfunction "2_2") (pintype "passive"))
      (node (ref "R24") (pin "2") (pinfunction "2_2") (pintype "passive"))
    )
    (net (code "37") (name "R_INPUT") (class "Default")
      (node (ref "IC4") (pin "3") (pinfunction "IN+_3") (pintype "bidirectional"))
      (node (ref "R1") (pin "2") (pinfunction "2_2") (pintype "passive"))
      (node (ref "X3") (pin "1") (pinfunction "S_1") (pintype "passive"))
    )
    (net (code "38") (name "R_STATOR_N") (class "Default")
      (node (ref "C28") (pin "2") (pinfunction "2_2") (pintype "passive"))
      (node (ref "J3") (pin "3") (pinfunction "3_3") (pintype "bidirectional"))
      (node (ref "R28") (pin "2") (pinfunction "2_2") (pintype "passive"))
    )
    (net (code "39") (name "R_STATOR_P") (class "Default")
      (node (ref "C32") (pin "2") (pinfunction "2_2") (pintype "passive"))
      (node (ref "J3") (pin "1") (pinfunction "1_1") (pintype "bidirectional"))
      (node (ref "R27") (pin "2") (pinfunction "2_2") (pintype "passive"))
    )
    (net (code "40") (name "unconnected-(H1-MOUNT-PadB4,1)") (class "Default")
      (node (ref "H1") (pin "B4,1") (pinfunction "MOUNT_B4,1") (pintype "passive"))
    )
    (net (code "41") (name "unconnected-(H2-MOUNT-PadB4,1)") (class "Default")
      (node (ref "H2") (pin "B4,1") (pinfunction "MOUNT_B4,1") (pintype "passive"))
    )
    (net (code "42") (name "unconnected-(H3-MOUNT-PadB4,1)") (class "Default")
      (node (ref "H3") (pin "B4,1") (pinfunction "MOUNT_B4,1") (pintype "passive"))
    )
    (net (code "43") (name "unconnected-(H4-MOUNT-PadB4,1)") (class "Default")
      (node (ref "H4") (pin "B4,1") (pinfunction "MOUNT_B4,1") (pintype "passive"))
    )
    (net (code "44") (name "unconnected-(IC1-VOS_TRIM1-Pad1)") (class "Default")
      (node (ref "IC1") (pin "1") (pinfunction "VOS_TRIM1_1") (pintype "bidirectional"))
    )
    (net (code "45") (name "unconnected-(IC1-VOS_TRIM2-Pad8)") (class "Default")
      (node (ref "IC1") (pin "8") (pinfunction "VOS_TRIM2_8") (pintype "bidirectional"))
    )
    (net (code "46") (name "unconnected-(IC2-VOS_TRIM1-Pad1)") (class "Default")
      (node (ref "IC2") (pin "1") (pinfunction "VOS_TRIM1_1") (pintype "bidirectional"))
    )
    (net (code "47") (name "unconnected-(IC2-VOS_TRIM2-Pad8)") (class "Default")
      (node (ref "IC2") (pin "8") (pinfunction "VOS_TRIM2_8") (pintype "bidirectional"))
    )
    (net (code "48") (name "unconnected-(IC3-VOS_TRIM1-Pad1)") (class "Default")
      (node (ref "IC3") (pin "1") (pinfunction "VOS_TRIM1_1") (pintype "bidirectional"))
    )
    (net (code "49") (name "unconnected-(IC3-VOS_TRIM2-Pad8)") (class "Default")
      (node (ref "IC3") (pin "8") (pinfunction "VOS_TRIM2_8") (pintype "bidirectional"))
    )
    (net (code "50") (name "unconnected-(IC4-VOS_TRIM1-Pad1)") (class "Default")
      (node (ref "IC4") (pin "1") (pinfunction "VOS_TRIM1_1") (pintype "bidirectional"))
    )
    (net (code "51") (name "unconnected-(IC4-VOS_TRIM2-Pad8)") (class "Default")
      (node (ref "IC4") (pin "8") (pinfunction "VOS_TRIM2_8") (pintype "bidirectional"))
    )
  )
)
